# ssc_32u_power_board.net
KiCad netlist of a schematic drawn in EAGLE
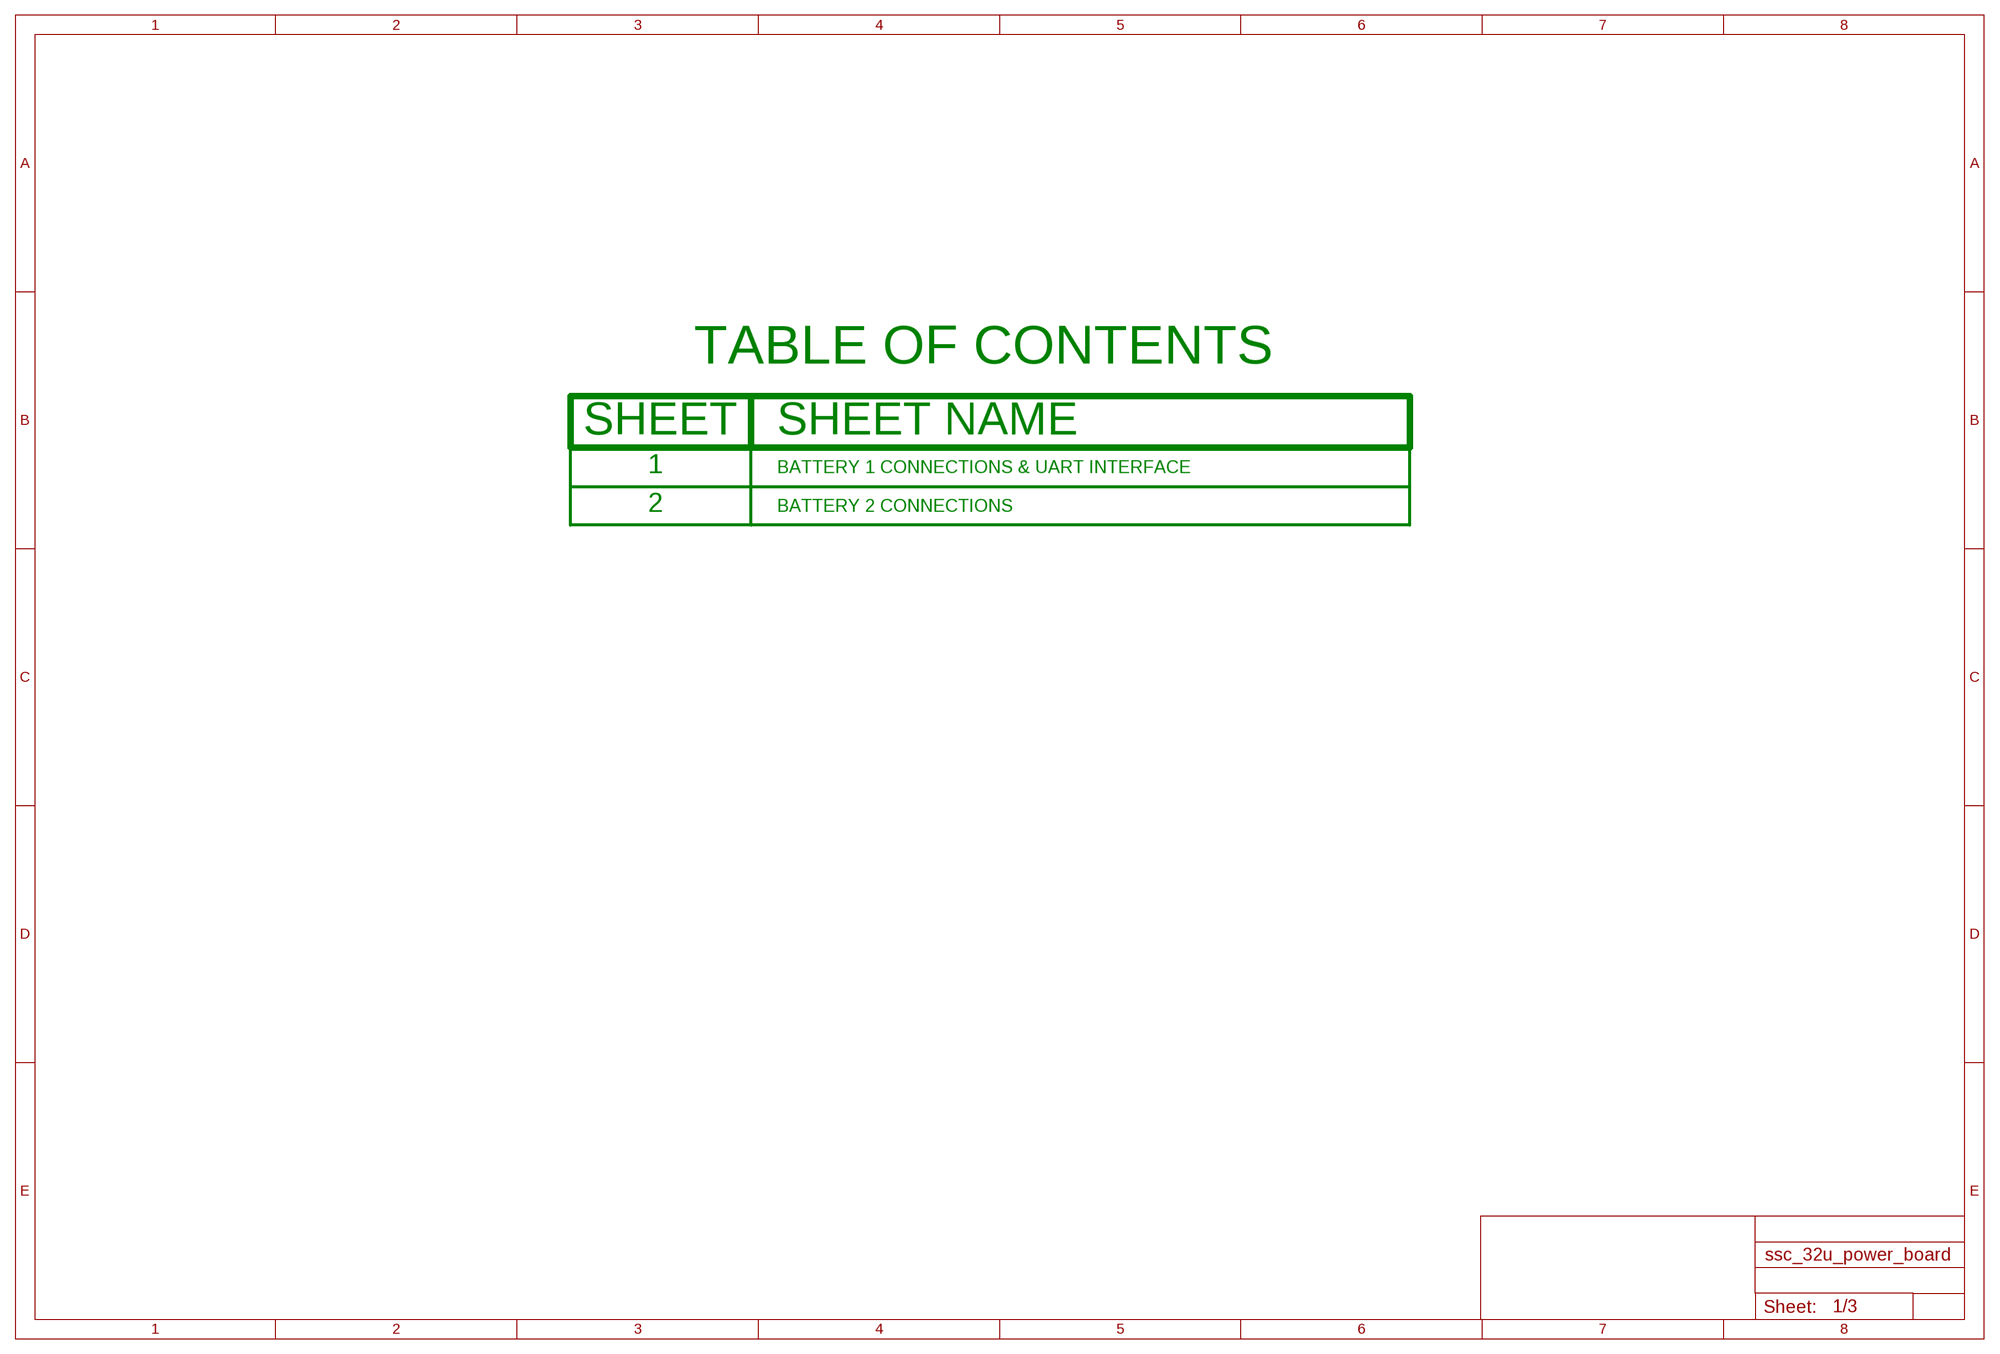
[diagram p0: schematic, sheet 1]
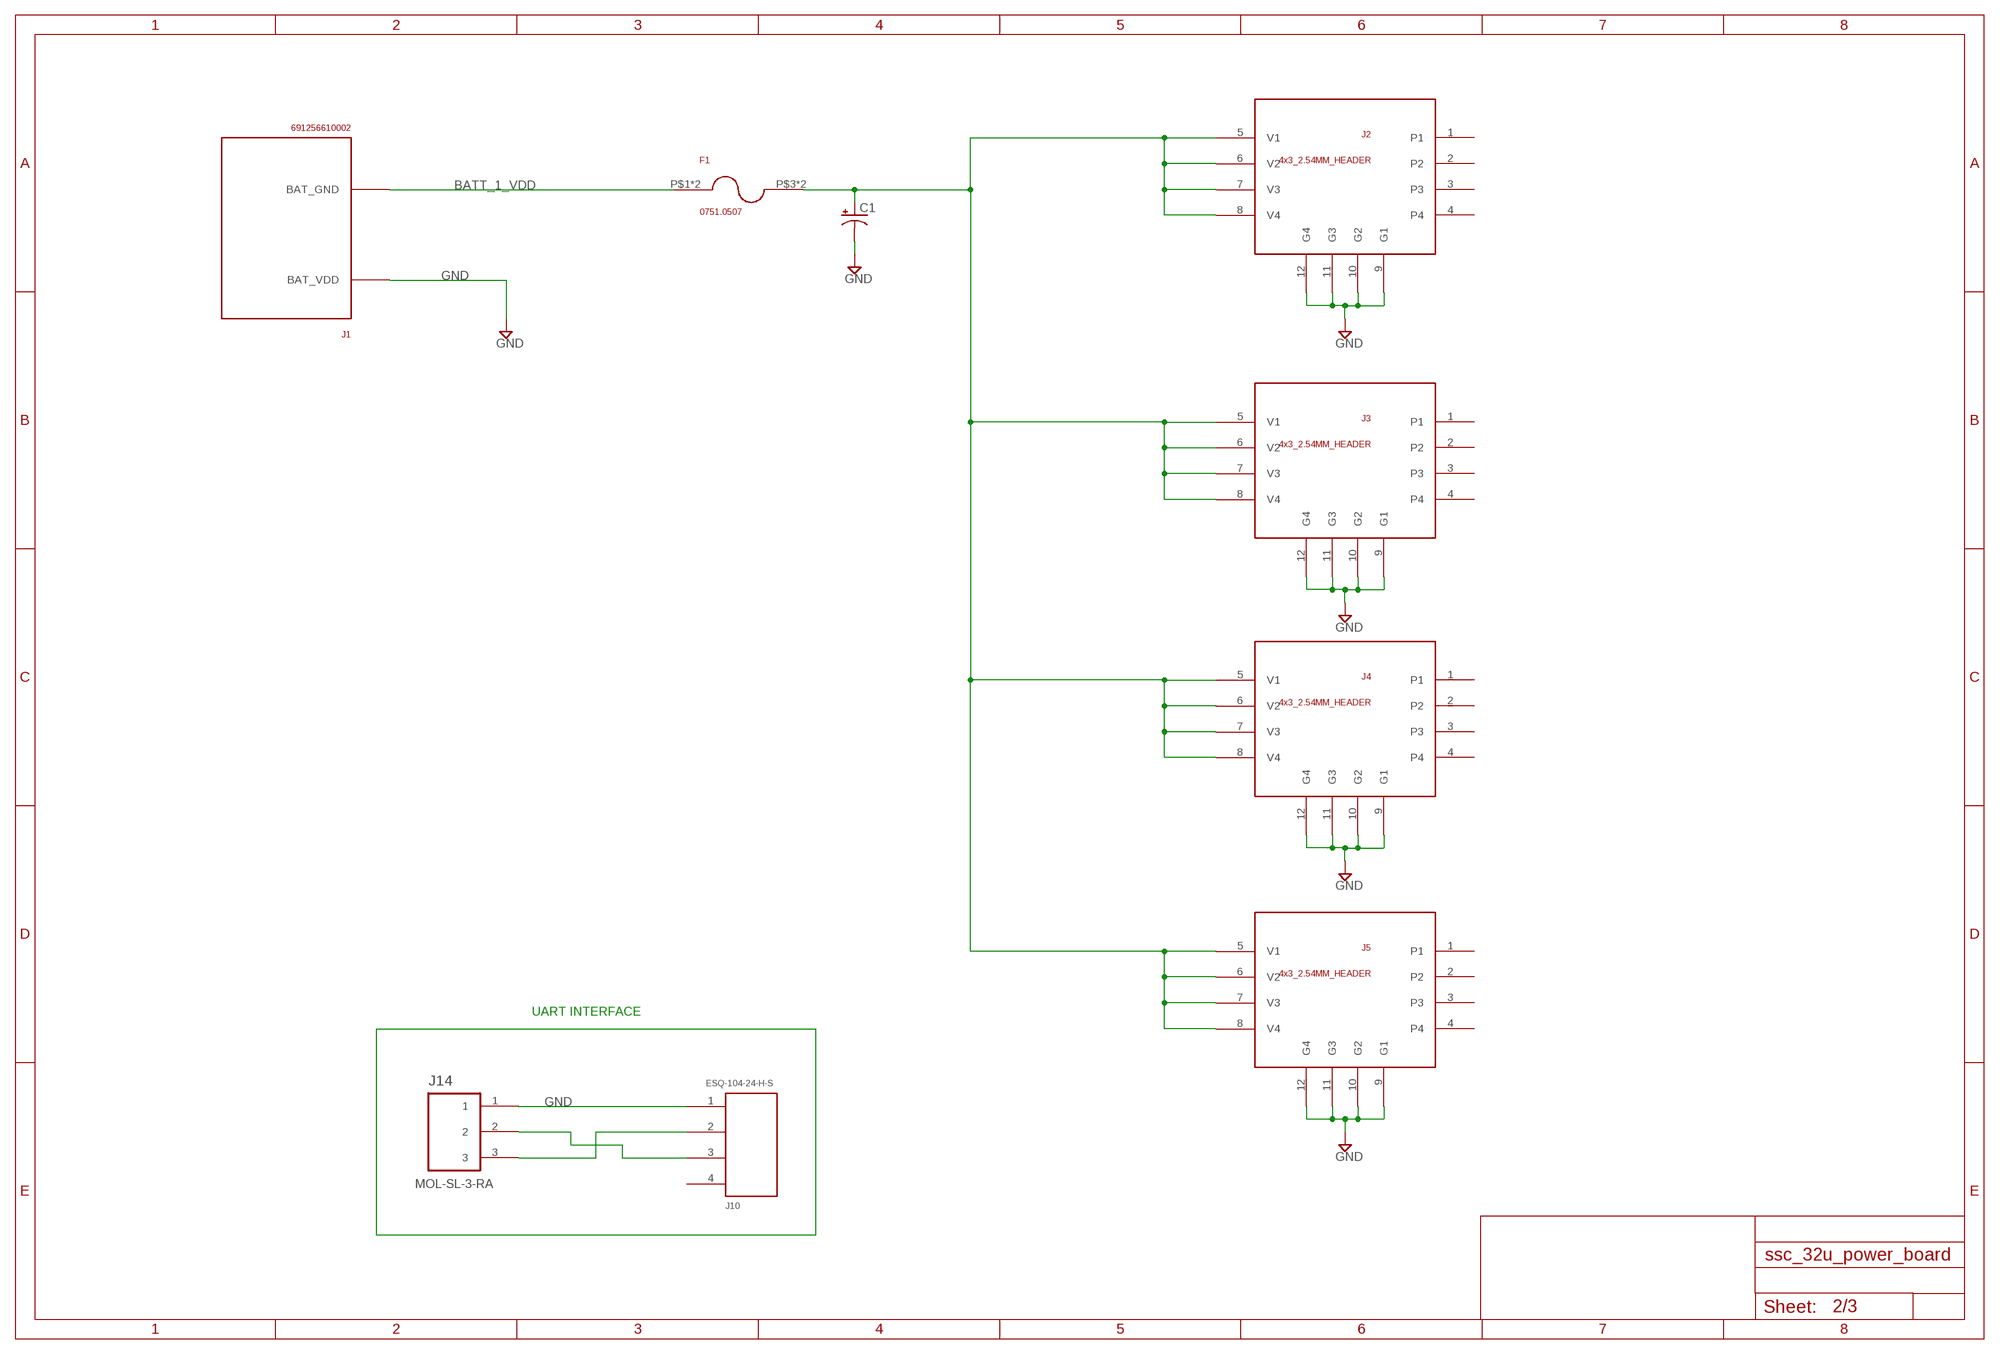
[diagram p1: schematic, sheet 2]
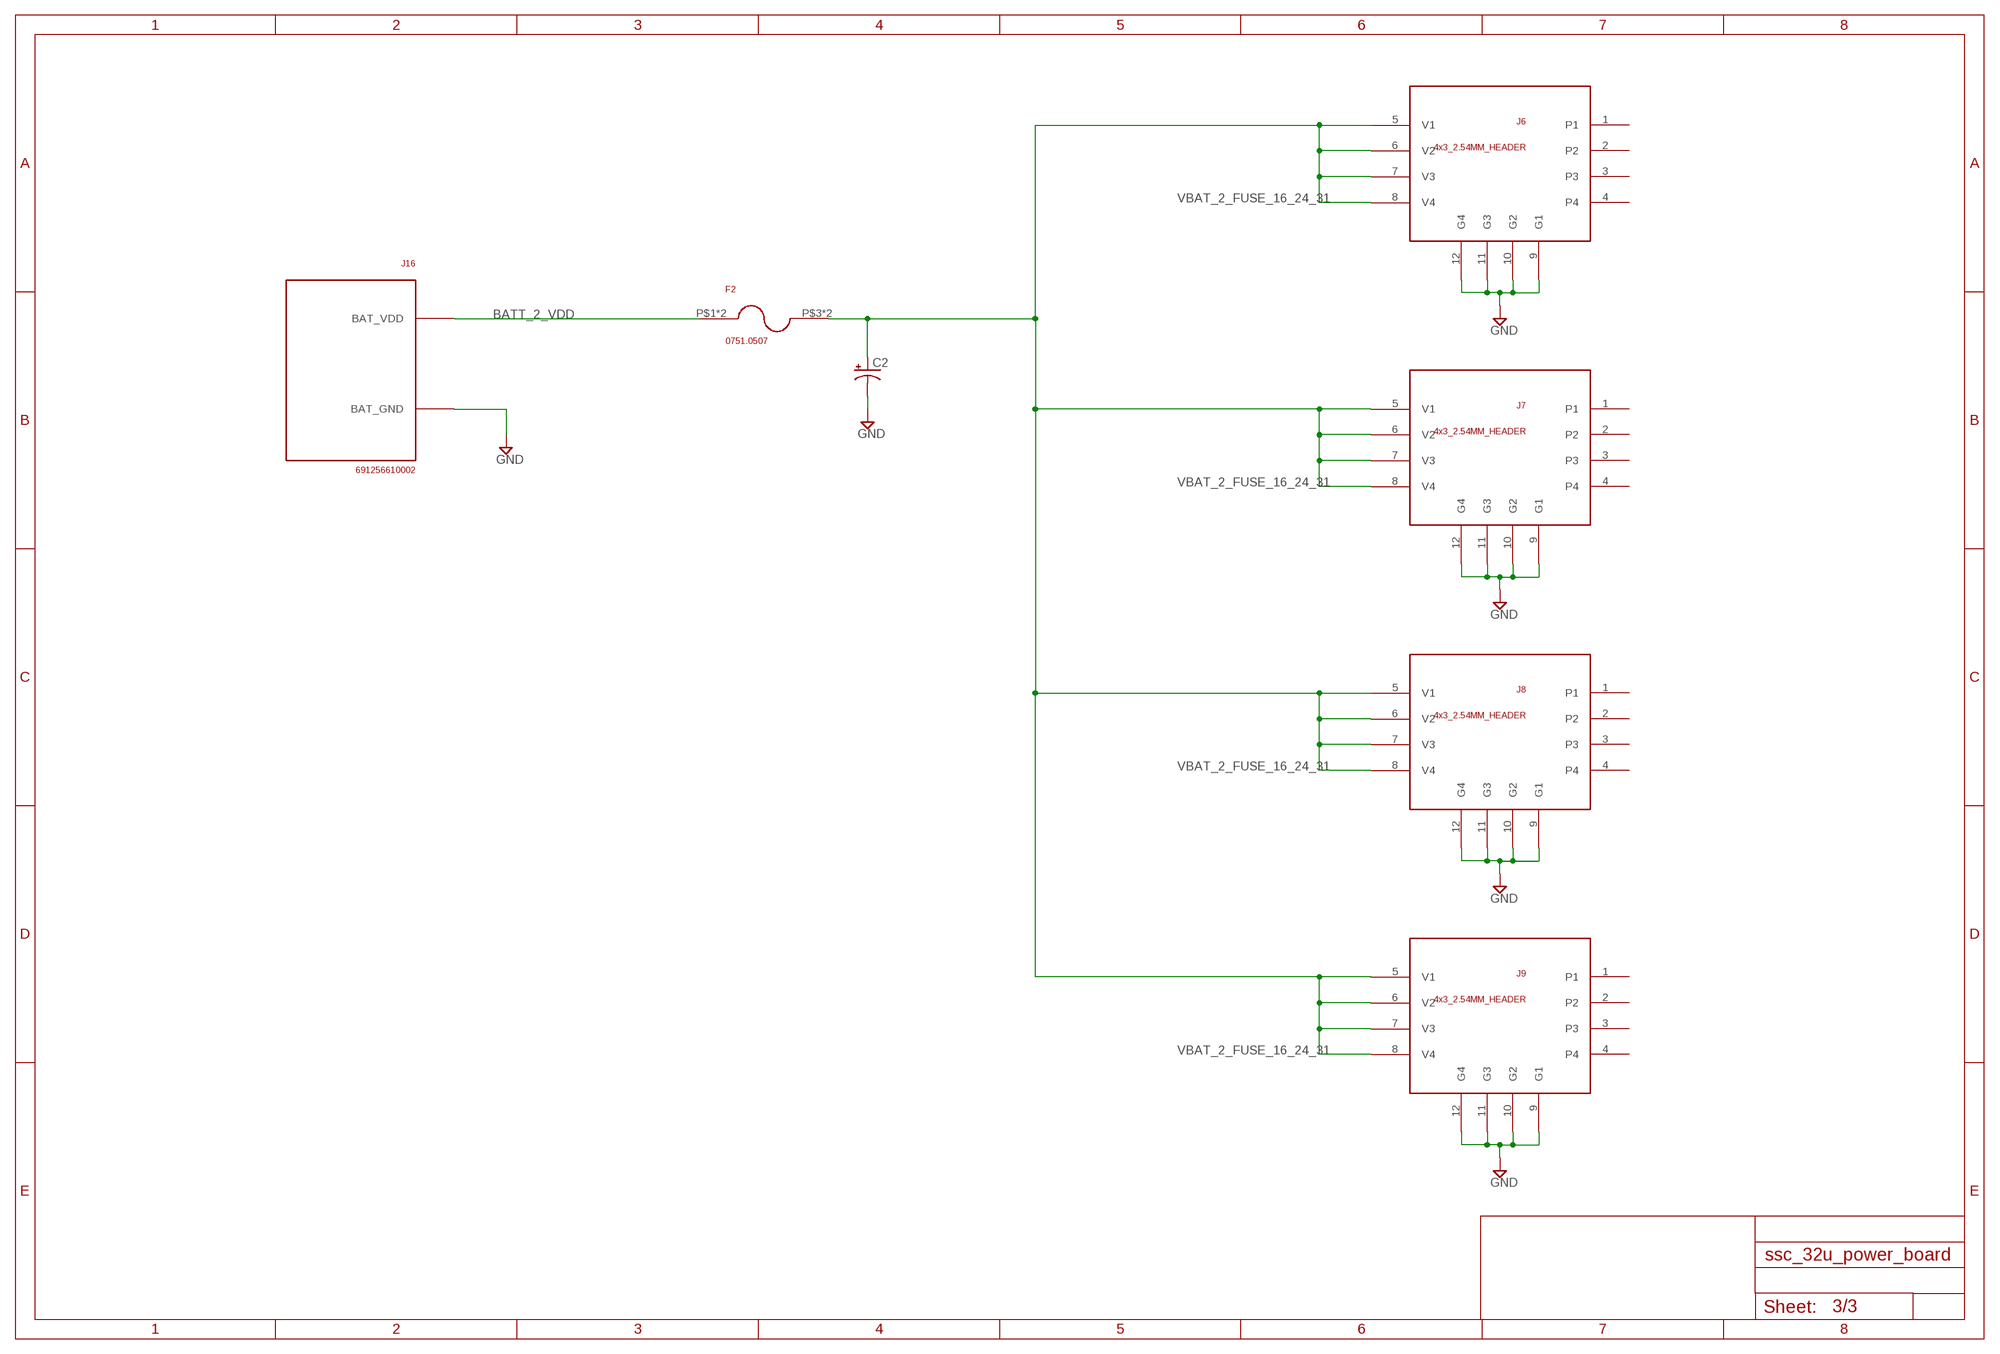
[diagram p2: schematic, sheet 3]

(export (version "E")
  (design (tool "Eeschema 10.0.6"))
  (components
    (comp (ref "C1")
      (value "CPOL-USE5-13")
      (footprint "eagle-import:E5-13")
      (libsource (lib "eagle-import") (part "CPOL-USE5-13"))
    )
    (comp (ref "F1")
      (value "0751.0507")
      (footprint "eagle-import:0751.0507")
      (fields (field (name "MANUFACTURER") "Schurter Inc."))
      (libsource (lib "eagle-import") (part "0751.0507"))
    )
    (comp (ref "J1")
      (value "691256610002")
      (footprint "eagle-import:691256610002")
      (fields (field (name "MANUFACTURER") "Wurth Electronics Inc."))
      (libsource (lib "eagle-import") (part "691256610002"))
    )
    (comp (ref "J2")
      (value "4x3_2.54MM_HEADER")
      (footprint "eagle-import:2X_ESQ-104-24-H-S__HMTSW-104-08-G-S-380")
      (libsource (lib "eagle-import") (part "2X_ESQ-104-24-H-S__HMTSW-104-08-G-S-380"))
    )
    (comp (ref "J3")
      (value "4x3_2.54MM_HEADER")
      (footprint "eagle-import:2X_ESQ-104-24-H-S__HMTSW-104-08-G-S-380")
      (libsource (lib "eagle-import") (part "2X_ESQ-104-24-H-S__HMTSW-104-08-G-S-380"))
    )
    (comp (ref "J4")
      (value "4x3_2.54MM_HEADER")
      (footprint "eagle-import:2X_ESQ-104-24-H-S__HMTSW-104-08-G-S-380")
      (libsource (lib "eagle-import") (part "2X_ESQ-104-24-H-S__HMTSW-104-08-G-S-380"))
    )
    (comp (ref "J5")
      (value "4x3_2.54MM_HEADER")
      (footprint "eagle-import:2X_ESQ-104-24-H-S__HMTSW-104-08-G-S-380")
      (libsource (lib "eagle-import") (part "2X_ESQ-104-24-H-S__HMTSW-104-08-G-S-380"))
    )
    (comp (ref "J10")
      (value "ESQ-104-24-H-S")
      (footprint "eagle-import:ESQ-104-24-H-S")
      (fields (field (name "MANUFACTURER") "Samtec"))
      (libsource (lib "eagle-import") (part "ESQ-104-24-H-S"))
    )
    (comp (ref "J14")
      (value "MOL-SL-3-RA")
      (footprint "eagle-import:MOLSL-3-RA")
      (fields (field (name "MANUFACTURER") "Molex"))
      (libsource (lib "eagle-import") (part "MOLSL_3PIN_RA_SL3RA"))
    )
    (comp (ref "C2")
      (value "CPOL-USE5-13")
      (footprint "eagle-import:E5-13")
      (libsource (lib "eagle-import") (part "CPOL-USE5-13"))
    )
    (comp (ref "F2")
      (value "0751.0507")
      (footprint "eagle-import:0751.0507")
      (fields (field (name "MANUFACTURER") "Schurter Inc."))
      (libsource (lib "eagle-import") (part "0751.0507"))
    )
    (comp (ref "J6")
      (value "4x3_2.54MM_HEADER")
      (footprint "eagle-import:2X_ESQ-104-24-H-S__HMTSW-104-08-G-S-380")
      (libsource (lib "eagle-import") (part "2X_ESQ-104-24-H-S__HMTSW-104-08-G-S-380"))
    )
    (comp (ref "J7")
      (value "4x3_2.54MM_HEADER")
      (footprint "eagle-import:2X_ESQ-104-24-H-S__HMTSW-104-08-G-S-380")
      (libsource (lib "eagle-import") (part "2X_ESQ-104-24-H-S__HMTSW-104-08-G-S-380"))
    )
    (comp (ref "J8")
      (value "4x3_2.54MM_HEADER")
      (footprint "eagle-import:2X_ESQ-104-24-H-S__HMTSW-104-08-G-S-380")
      (libsource (lib "eagle-import") (part "2X_ESQ-104-24-H-S__HMTSW-104-08-G-S-380"))
    )
    (comp (ref "J9")
      (value "4x3_2.54MM_HEADER")
      (footprint "eagle-import:2X_ESQ-104-24-H-S__HMTSW-104-08-G-S-380")
      (libsource (lib "eagle-import") (part "2X_ESQ-104-24-H-S__HMTSW-104-08-G-S-380"))
    )
    (comp (ref "J16")
      (value "691256610002")
      (footprint "eagle-import:691256610002")
      (fields (field (name "MANUFACTURER") "Wurth Electronics Inc."))
      (libsource (lib "eagle-import") (part "691256610002"))
    )
  )
  (nets
    (net (code "1") (name "BATT_1_VDD") (class "Default")
      (node (ref "F1") (pin "P$1") (pinfunction "P$1_P$1") (pintype "bidirectional"))
      (node (ref "F1") (pin "P$2") (pinfunction "P$1_P$2") (pintype "bidirectional"))
      (node (ref "J1") (pin "P$1") (pinfunction "BAT_GND_P$1") (pintype "bidirectional"))
      (node (ref "J1") (pin "P$2") (pinfunction "BAT_GND_P$2") (pintype "bidirectional"))
    )
    (net (code "2") (name "BATT_2_VDD") (class "Default")
      (node (ref "F2") (pin "P$1") (pinfunction "P$1_P$1") (pintype "bidirectional"))
      (node (ref "F2") (pin "P$2") (pinfunction "P$1_P$2") (pintype "bidirectional"))
      (node (ref "J16") (pin "P$3") (pinfunction "BAT_VDD_P$3") (pintype "bidirectional"))
      (node (ref "J16") (pin "P$4") (pinfunction "BAT_VDD_P$4") (pintype "bidirectional"))
    )
    (net (code "3") (name "GND") (class "Default")
      (node (ref "C1") (pin "-") (pinfunction "-_-") (pintype "passive"))
      (node (ref "C2") (pin "-") (pinfunction "-_-") (pintype "passive"))
      (node (ref "J1") (pin "P$3") (pinfunction "BAT_VDD_P$3") (pintype "bidirectional"))
      (node (ref "J1") (pin "P$4") (pinfunction "BAT_VDD_P$4") (pintype "bidirectional"))
      (node (ref "J10") (pin "1") (pinfunction "P$1_1") (pintype "bidirectional"))
      (node (ref "J14") (pin "1") (pinfunction "1_1") (pintype "bidirectional"))
      (node (ref "J16") (pin "P$1") (pinfunction "BAT_GND_P$1") (pintype "bidirectional"))
      (node (ref "J16") (pin "P$2") (pinfunction "BAT_GND_P$2") (pintype "bidirectional"))
      (node (ref "J2") (pin "10") (pinfunction "G2_10") (pintype "bidirectional"))
      (node (ref "J2") (pin "11") (pinfunction "G3_11") (pintype "bidirectional"))
      (node (ref "J2") (pin "12") (pinfunction "G4_12") (pintype "bidirectional"))
      (node (ref "J2") (pin "9") (pinfunction "G1_9") (pintype "bidirectional"))
      (node (ref "J3") (pin "10") (pinfunction "G2_10") (pintype "bidirectional"))
      (node (ref "J3") (pin "11") (pinfunction "G3_11") (pintype "bidirectional"))
      (node (ref "J3") (pin "12") (pinfunction "G4_12") (pintype "bidirectional"))
      (node (ref "J3") (pin "9") (pinfunction "G1_9") (pintype "bidirectional"))
      (node (ref "J4") (pin "10") (pinfunction "G2_10") (pintype "bidirectional"))
      (node (ref "J4") (pin "11") (pinfunction "G3_11") (pintype "bidirectional"))
      (node (ref "J4") (pin "12") (pinfunction "G4_12") (pintype "bidirectional"))
      (node (ref "J4") (pin "9") (pinfunction "G1_9") (pintype "bidirectional"))
      (node (ref "J5") (pin "10") (pinfunction "G2_10") (pintype "bidirectional"))
      (node (ref "J5") (pin "11") (pinfunction "G3_11") (pintype "bidirectional"))
      (node (ref "J5") (pin "12") (pinfunction "G4_12") (pintype "bidirectional"))
      (node (ref "J5") (pin "9") (pinfunction "G1_9") (pintype "bidirectional"))
      (node (ref "J6") (pin "10") (pinfunction "G2_10") (pintype "bidirectional"))
      (node (ref "J6") (pin "11") (pinfunction "G3_11") (pintype "bidirectional"))
      (node (ref "J6") (pin "12") (pinfunction "G4_12") (pintype "bidirectional"))
      (node (ref "J6") (pin "9") (pinfunction "G1_9") (pintype "bidirectional"))
      (node (ref "J7") (pin "10") (pinfunction "G2_10") (pintype "bidirectional"))
      (node (ref "J7") (pin "11") (pinfunction "G3_11") (pintype "bidirectional"))
      (node (ref "J7") (pin "12") (pinfunction "G4_12") (pintype "bidirectional"))
      (node (ref "J7") (pin "9") (pinfunction "G1_9") (pintype "bidirectional"))
      (node (ref "J8") (pin "10") (pinfunction "G2_10") (pintype "bidirectional"))
      (node (ref "J8") (pin "11") (pinfunction "G3_11") (pintype "bidirectional"))
      (node (ref "J8") (pin "12") (pinfunction "G4_12") (pintype "bidirectional"))
      (node (ref "J8") (pin "9") (pinfunction "G1_9") (pintype "bidirectional"))
      (node (ref "J9") (pin "10") (pinfunction "G2_10") (pintype "bidirectional"))
      (node (ref "J9") (pin "11") (pinfunction "G3_11") (pintype "bidirectional"))
      (node (ref "J9") (pin "12") (pinfunction "G4_12") (pintype "bidirectional"))
      (node (ref "J9") (pin "9") (pinfunction "G1_9") (pintype "bidirectional"))
    )
    (net (code "4") (name "Net-(J2-V1)") (class "Default")
      (node (ref "C1") (pin "+") (pinfunction "+_+") (pintype "passive"))
      (node (ref "F1") (pin "P$3") (pinfunction "P$2_P$3") (pintype "bidirectional"))
      (node (ref "F1") (pin "P$4") (pinfunction "P$2_P$4") (pintype "bidirectional"))
      (node (ref "J2") (pin "5") (pinfunction "V1_5") (pintype "bidirectional"))
      (node (ref "J2") (pin "6") (pinfunction "V2_6") (pintype "bidirectional"))
      (node (ref "J2") (pin "7") (pinfunction "V3_7") (pintype "bidirectional"))
      (node (ref "J2") (pin "8") (pinfunction "V4_8") (pintype "bidirectional"))
      (node (ref "J3") (pin "5") (pinfunction "V1_5") (pintype "bidirectional"))
      (node (ref "J3") (pin "6") (pinfunction "V2_6") (pintype "bidirectional"))
      (node (ref "J3") (pin "7") (pinfunction "V3_7") (pintype "bidirectional"))
      (node (ref "J3") (pin "8") (pinfunction "V4_8") (pintype "bidirectional"))
      (node (ref "J4") (pin "5") (pinfunction "V1_5") (pintype "bidirectional"))
      (node (ref "J4") (pin "6") (pinfunction "V2_6") (pintype "bidirectional"))
      (node (ref "J4") (pin "7") (pinfunction "V3_7") (pintype "bidirectional"))
      (node (ref "J4") (pin "8") (pinfunction "V4_8") (pintype "bidirectional"))
      (node (ref "J5") (pin "5") (pinfunction "V1_5") (pintype "bidirectional"))
      (node (ref "J5") (pin "6") (pinfunction "V2_6") (pintype "bidirectional"))
      (node (ref "J5") (pin "7") (pinfunction "V3_7") (pintype "bidirectional"))
      (node (ref "J5") (pin "8") (pinfunction "V4_8") (pintype "bidirectional"))
    )
    (net (code "5") (name "Net-(J10-P$2)") (class "Default")
      (node (ref "J10") (pin "2") (pinfunction "P$2_2") (pintype "bidirectional"))
      (node (ref "J14") (pin "3") (pinfunction "3_3") (pintype "bidirectional"))
    )
    (net (code "6") (name "Net-(J10-P$3)") (class "Default")
      (node (ref "J10") (pin "3") (pinfunction "P$3_3") (pintype "bidirectional"))
      (node (ref "J14") (pin "2") (pinfunction "2_2") (pintype "bidirectional"))
    )
    (net (code "7") (name "VBAT_2_FUSE_16_24_31") (class "Default")
      (node (ref "C2") (pin "+") (pinfunction "+_+") (pintype "passive"))
      (node (ref "F2") (pin "P$3") (pinfunction "P$2_P$3") (pintype "bidirectional"))
      (node (ref "F2") (pin "P$4") (pinfunction "P$2_P$4") (pintype "bidirectional"))
      (node (ref "J6") (pin "5") (pinfunction "V1_5") (pintype "bidirectional"))
      (node (ref "J6") (pin "6") (pinfunction "V2_6") (pintype "bidirectional"))
      (node (ref "J6") (pin "7") (pinfunction "V3_7") (pintype "bidirectional"))
      (node (ref "J6") (pin "8") (pinfunction "V4_8") (pintype "bidirectional"))
      (node (ref "J7") (pin "5") (pinfunction "V1_5") (pintype "bidirectional"))
      (node (ref "J7") (pin "6") (pinfunction "V2_6") (pintype "bidirectional"))
      (node (ref "J7") (pin "7") (pinfunction "V3_7") (pintype "bidirectional"))
      (node (ref "J7") (pin "8") (pinfunction "V4_8") (pintype "bidirectional"))
      (node (ref "J8") (pin "5") (pinfunction "V1_5") (pintype "bidirectional"))
      (node (ref "J8") (pin "6") (pinfunction "V2_6") (pintype "bidirectional"))
      (node (ref "J8") (pin "7") (pinfunction "V3_7") (pintype "bidirectional"))
      (node (ref "J8") (pin "8") (pinfunction "V4_8") (pintype "bidirectional"))
      (node (ref "J9") (pin "5") (pinfunction "V1_5") (pintype "bidirectional"))
      (node (ref "J9") (pin "6") (pinfunction "V2_6") (pintype "bidirectional"))
      (node (ref "J9") (pin "7") (pinfunction "V3_7") (pintype "bidirectional"))
      (node (ref "J9") (pin "8") (pinfunction "V4_8") (pintype "bidirectional"))
    )
    (net (code "8") (name "unconnected-(J2-P1-Pad1)") (class "Default")
      (node (ref "J2") (pin "1") (pinfunction "P1_1") (pintype "bidirectional"))
    )
    (net (code "9") (name "unconnected-(J2-P2-Pad2)") (class "Default")
      (node (ref "J2") (pin "2") (pinfunction "P2_2") (pintype "bidirectional"))
    )
    (net (code "10") (name "unconnected-(J2-P3-Pad3)") (class "Default")
      (node (ref "J2") (pin "3") (pinfunction "P3_3") (pintype "bidirectional"))
    )
    (net (code "11") (name "unconnected-(J2-P4-Pad4)") (class "Default")
      (node (ref "J2") (pin "4") (pinfunction "P4_4") (pintype "bidirectional"))
    )
    (net (code "12") (name "unconnected-(J3-P1-Pad1)") (class "Default")
      (node (ref "J3") (pin "1") (pinfunction "P1_1") (pintype "bidirectional"))
    )
    (net (code "13") (name "unconnected-(J3-P2-Pad2)") (class "Default")
      (node (ref "J3") (pin "2") (pinfunction "P2_2") (pintype "bidirectional"))
    )
    (net (code "14") (name "unconnected-(J3-P3-Pad3)") (class "Default")
      (node (ref "J3") (pin "3") (pinfunction "P3_3") (pintype "bidirectional"))
    )
    (net (code "15") (name "unconnected-(J3-P4-Pad4)") (class "Default")
      (node (ref "J3") (pin "4") (pinfunction "P4_4") (pintype "bidirectional"))
    )
    (net (code "16") (name "unconnected-(J4-P1-Pad1)") (class "Default")
      (node (ref "J4") (pin "1") (pinfunction "P1_1") (pintype "bidirectional"))
    )
    (net (code "17") (name "unconnected-(J4-P2-Pad2)") (class "Default")
      (node (ref "J4") (pin "2") (pinfunction "P2_2") (pintype "bidirectional"))
    )
    (net (code "18") (name "unconnected-(J4-P3-Pad3)") (class "Default")
      (node (ref "J4") (pin "3") (pinfunction "P3_3") (pintype "bidirectional"))
    )
    (net (code "19") (name "unconnected-(J4-P4-Pad4)") (class "Default")
      (node (ref "J4") (pin "4") (pinfunction "P4_4") (pintype "bidirectional"))
    )
    (net (code "20") (name "unconnected-(J5-P1-Pad1)") (class "Default")
      (node (ref "J5") (pin "1") (pinfunction "P1_1") (pintype "bidirectional"))
    )
    (net (code "21") (name "unconnected-(J5-P2-Pad2)") (class "Default")
      (node (ref "J5") (pin "2") (pinfunction "P2_2") (pintype "bidirectional"))
    )
    (net (code "22") (name "unconnected-(J5-P3-Pad3)") (class "Default")
      (node (ref "J5") (pin "3") (pinfunction "P3_3") (pintype "bidirectional"))
    )
    (net (code "23") (name "unconnected-(J5-P4-Pad4)") (class "Default")
      (node (ref "J5") (pin "4") (pinfunction "P4_4") (pintype "bidirectional"))
    )
    (net (code "24") (name "unconnected-(J6-P1-Pad1)") (class "Default")
      (node (ref "J6") (pin "1") (pinfunction "P1_1") (pintype "bidirectional"))
    )
    (net (code "25") (name "unconnected-(J6-P2-Pad2)") (class "Default")
      (node (ref "J6") (pin "2") (pinfunction "P2_2") (pintype "bidirectional"))
    )
    (net (code "26") (name "unconnected-(J6-P3-Pad3)") (class "Default")
      (node (ref "J6") (pin "3") (pinfunction "P3_3") (pintype "bidirectional"))
    )
    (net (code "27") (name "unconnected-(J6-P4-Pad4)") (class "Default")
      (node (ref "J6") (pin "4") (pinfunction "P4_4") (pintype "bidirectional"))
    )
    (net (code "28") (name "unconnected-(J7-P1-Pad1)") (class "Default")
      (node (ref "J7") (pin "1") (pinfunction "P1_1") (pintype "bidirectional"))
    )
    (net (code "29") (name "unconnected-(J7-P2-Pad2)") (class "Default")
      (node (ref "J7") (pin "2") (pinfunction "P2_2") (pintype "bidirectional"))
    )
    (net (code "30") (name "unconnected-(J7-P3-Pad3)") (class "Default")
      (node (ref "J7") (pin "3") (pinfunction "P3_3") (pintype "bidirectional"))
    )
    (net (code "31") (name "unconnected-(J7-P4-Pad4)") (class "Default")
      (node (ref "J7") (pin "4") (pinfunction "P4_4") (pintype "bidirectional"))
    )
    (net (code "32") (name "unconnected-(J8-P1-Pad1)") (class "Default")
      (node (ref "J8") (pin "1") (pinfunction "P1_1") (pintype "bidirectional"))
    )
    (net (code "33") (name "unconnected-(J8-P2-Pad2)") (class "Default")
      (node (ref "J8") (pin "2") (pinfunction "P2_2") (pintype "bidirectional"))
    )
    (net (code "34") (name "unconnected-(J8-P3-Pad3)") (class "Default")
      (node (ref "J8") (pin "3") (pinfunction "P3_3") (pintype "bidirectional"))
    )
    (net (code "35") (name "unconnected-(J8-P4-Pad4)") (class "Default")
      (node (ref "J8") (pin "4") (pinfunction "P4_4") (pintype "bidirectional"))
    )
    (net (code "36") (name "unconnected-(J9-P1-Pad1)") (class "Default")
      (node (ref "J9") (pin "1") (pinfunction "P1_1") (pintype "bidirectional"))
    )
    (net (code "37") (name "unconnected-(J9-P2-Pad2)") (class "Default")
      (node (ref "J9") (pin "2") (pinfunction "P2_2") (pintype "bidirectional"))
    )
    (net (code "38") (name "unconnected-(J9-P3-Pad3)") (class "Default")
      (node (ref "J9") (pin "3") (pinfunction "P3_3") (pintype "bidirectional"))
    )
    (net (code "39") (name "unconnected-(J9-P4-Pad4)") (class "Default")
      (node (ref "J9") (pin "4") (pinfunction "P4_4") (pintype "bidirectional"))
    )
    (net (code "40") (name "unconnected-(J10-P$4-Pad4)") (class "Default")
      (node (ref "J10") (pin "4") (pinfunction "P$4_4") (pintype "bidirectional"))
    )
  )
)
